# STM32PCB_Sch.net
KiCad netlist of a schematic drawn in Altium Designer
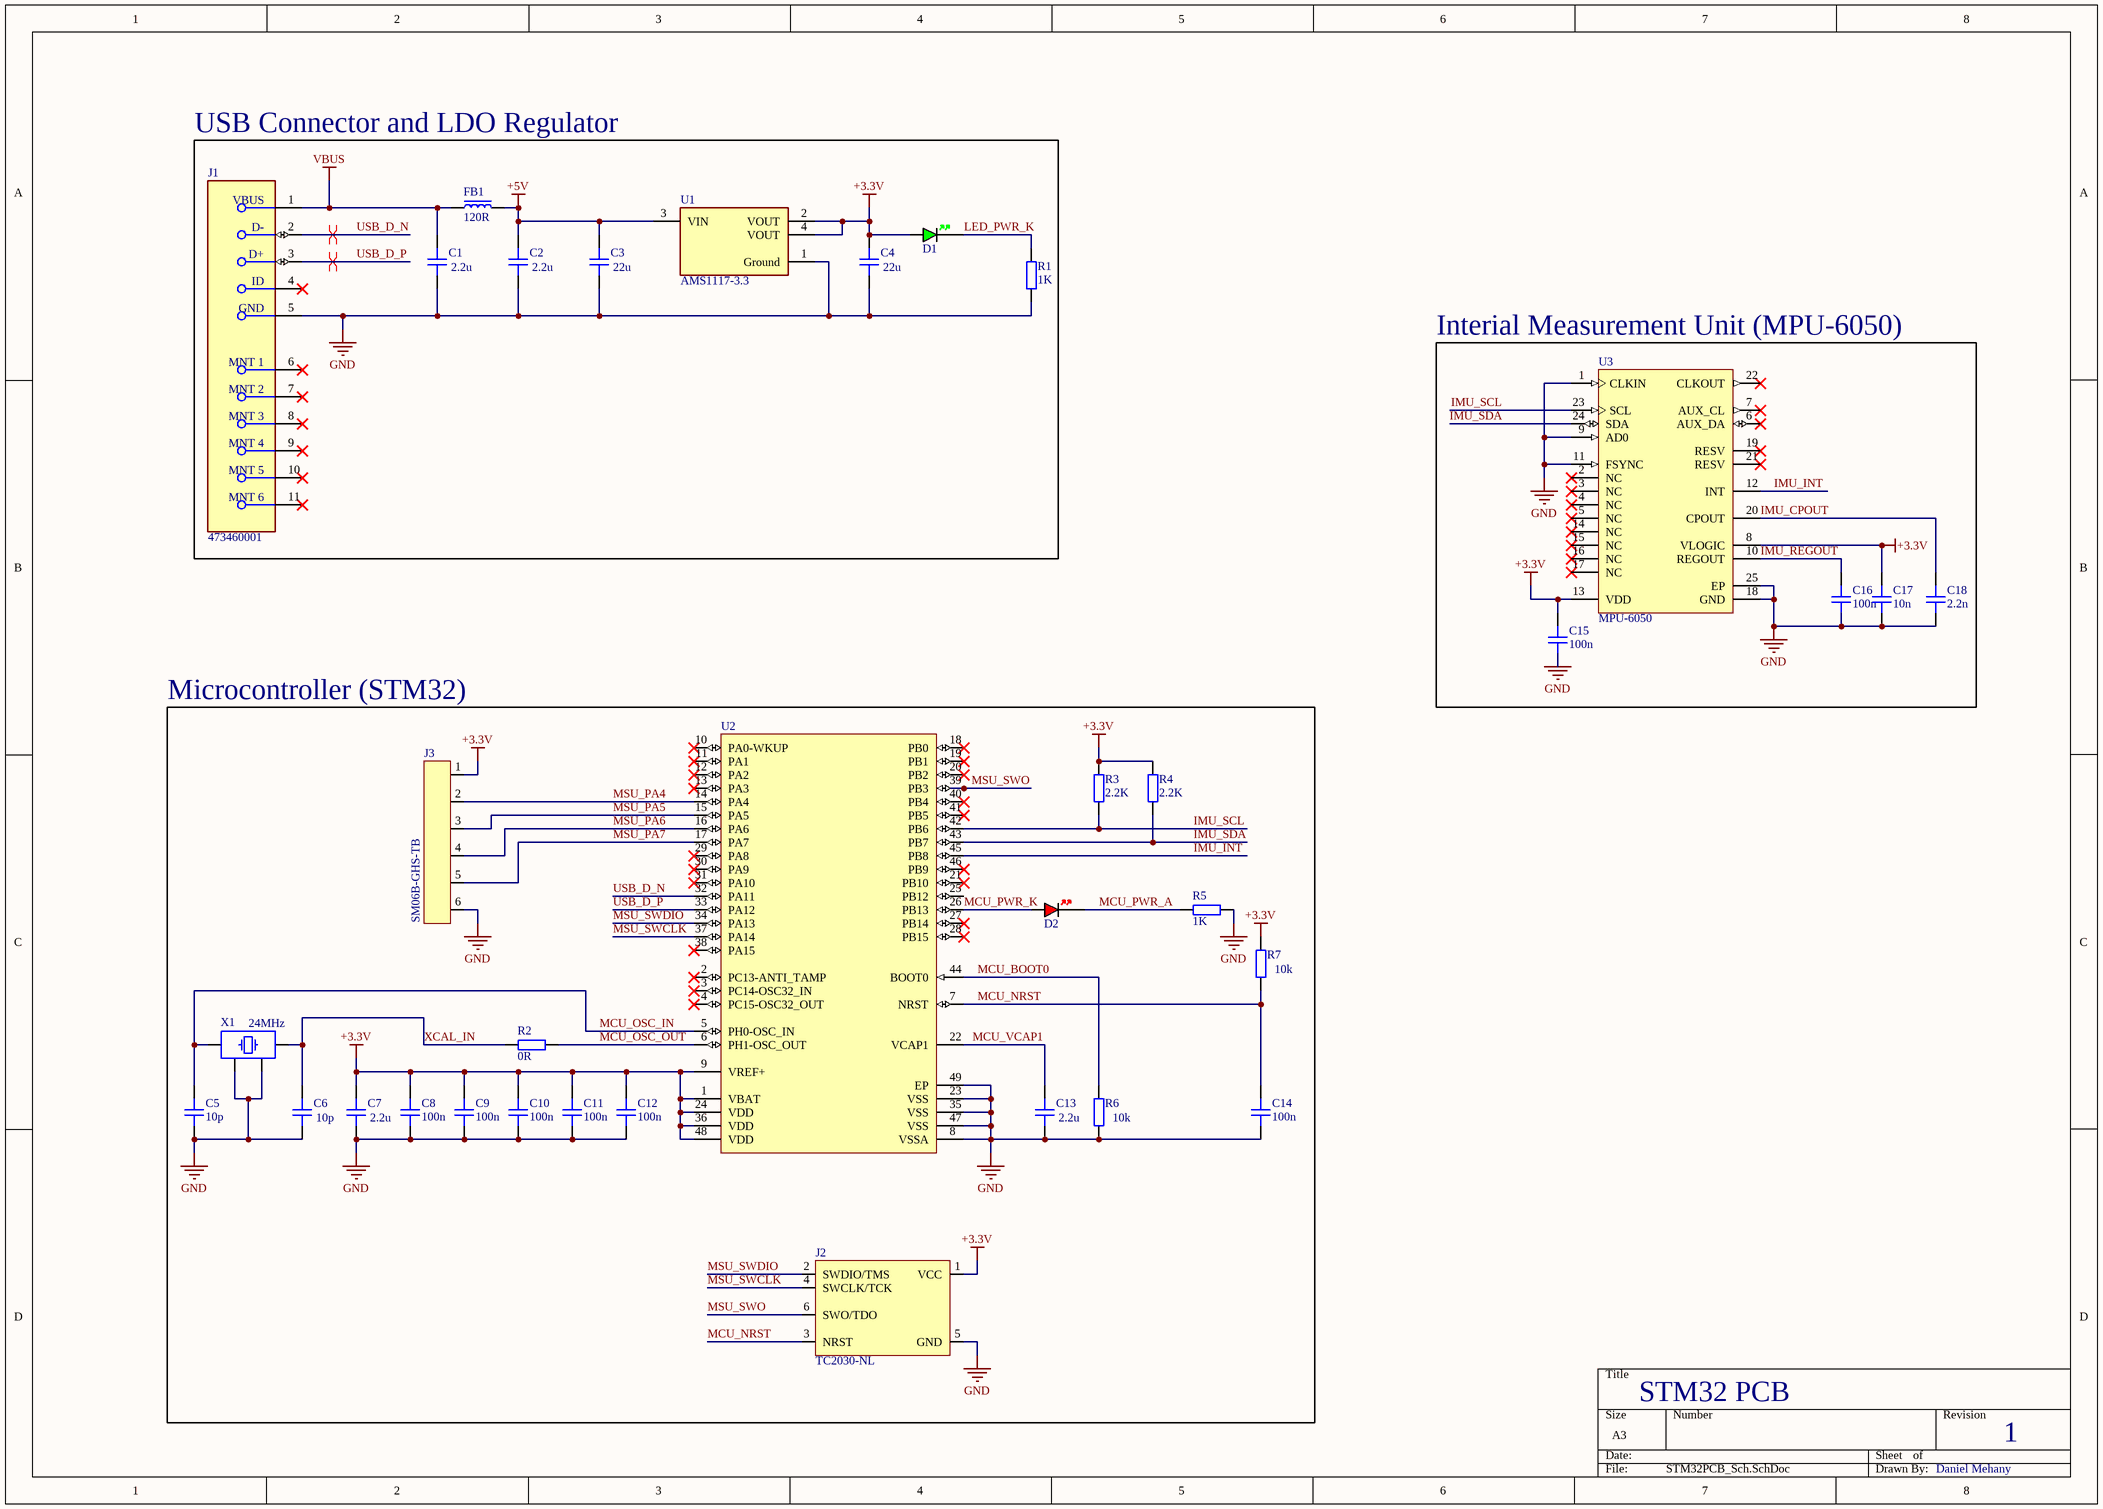
[diagram p0: STM32PCB_Sch.SchDoc]

(export (version "E")
  (design (tool "Eeschema 10.0.6"))
  (components
    (comp (ref "C1")
      (value "2.2u")
      (footprint "CAP_0603")
      (description "Capacitor SMD 0603")
      (libsource (lib "Online_Schematic_Library") (part "CAP_0603"))
    )
    (comp (ref "C2")
      (value "2.2u")
      (footprint "CAP_0603")
      (description "Capacitor SMD 0603")
      (libsource (lib "Online_Schematic_Library") (part "CAP_0603"))
    )
    (comp (ref "C3")
      (value "22u")
      (footprint "CAP_0603")
      (description "Capacitor SMD 0603")
      (libsource (lib "Online_Schematic_Library") (part "CAP_0603"))
    )
    (comp (ref "C4")
      (value "22u")
      (footprint "CAP_0603")
      (description "Capacitor SMD 0603")
      (libsource (lib "Online_Schematic_Library") (part "CAP_0603"))
    )
    (comp (ref "C5")
      (value "10p")
      (footprint "CAP_0402")
      (description "Capacitor SMD 0402")
      (libsource (lib "Online_Schematic_Library") (part "CAP_0402"))
    )
    (comp (ref "C6")
      (value "10p")
      (footprint "CAP_0402")
      (description "Capacitor SMD 0402")
      (libsource (lib "Online_Schematic_Library") (part "CAP_0402"))
    )
    (comp (ref "C7")
      (value "2.2u")
      (footprint "CAP_0603")
      (description "Capacitor SMD 0603")
      (libsource (lib "Online_Schematic_Library") (part "CAP_0603"))
    )
    (comp (ref "C8")
      (value "100n")
      (footprint "CAP_0402")
      (description "Capacitor SMD 0402")
      (fields (field (name "Comment") "C0402_16V"))
      (libsource (lib "Online_Schematic_Library") (part "CAP_0402"))
    )
    (comp (ref "C9")
      (value "100n")
      (footprint "CAP_0402")
      (description "Capacitor SMD 0402")
      (fields (field (name "Comment") "C0402_16V"))
      (libsource (lib "Online_Schematic_Library") (part "CAP_0402"))
    )
    (comp (ref "C10")
      (value "100n")
      (footprint "CAP_0402")
      (description "Capacitor SMD 0402")
      (fields (field (name "Comment") "C0402_16V"))
      (libsource (lib "Online_Schematic_Library") (part "CAP_0402"))
    )
    (comp (ref "C11")
      (value "100n")
      (footprint "CAP_0402")
      (description "Capacitor SMD 0402")
      (fields (field (name "Comment") "C0402_16V"))
      (libsource (lib "Online_Schematic_Library") (part "CAP_0402"))
    )
    (comp (ref "C12")
      (value "100n")
      (footprint "CAP_0402")
      (description "Capacitor SMD 0402")
      (fields (field (name "Comment") "C0402_16V"))
      (libsource (lib "Online_Schematic_Library") (part "CAP_0402"))
    )
    (comp (ref "C13")
      (value "2.2u")
      (footprint "CAP_0603")
      (description "Capacitor SMD 0603")
      (libsource (lib "Online_Schematic_Library") (part "CAP_0603"))
    )
    (comp (ref "C14")
      (value "100n")
      (footprint "CAP_0402")
      (description "Capacitor SMD 0402")
      (fields (field (name "Comment") "C0402_16V"))
      (libsource (lib "Online_Schematic_Library") (part "CAP_0402"))
    )
    (comp (ref "C15")
      (value "100n")
      (footprint "CAP_0402")
      (description "Capacitor SMD 0402")
      (fields (field (name "Comment") "C0402_16V"))
      (libsource (lib "Online_Schematic_Library") (part "CAP_0402"))
    )
    (comp (ref "C16")
      (value "100n")
      (footprint "CAP_0402")
      (description "Capacitor SMD 0402")
      (fields (field (name "Comment") "C0402_16V"))
      (libsource (lib "Online_Schematic_Library") (part "CAP_0402"))
    )
    (comp (ref "C17")
      (value "10n")
      (footprint "CAP_0402")
      (description "Capacitor SMD 0402")
      (fields (field (name "Comment") "C0402_16V"))
      (libsource (lib "Online_Schematic_Library") (part "CAP_0402"))
    )
    (comp (ref "C18")
      (value "2.2n")
      (footprint "CAP_0402")
      (description "Capacitor SMD 0402")
      (fields (field (name "Comment") "C0402_16V"))
      (libsource (lib "Online_Schematic_Library") (part "CAP_0402"))
    )
    (comp (ref "D1")
      (value "GREEN")
      (footprint "LED_0402_GREEN")
      (description "LED 0402 GREEN SMD")
      (libsource (lib "Online_Schematic_Library") (part "LED_0402_GREEN"))
    )
    (comp (ref "D2")
      (value "RED")
      (footprint "LED_0402_RED")
      (description "LED 0402 RED SMD")
      (libsource (lib "Online_Schematic_Library") (part "LED_0402_RED"))
    )
    (comp (ref "FB1")
      (value "120R")
      (footprint "FB_0603")
      (description "Ferrite Bead SMD 0603")
      (libsource (lib "Online_Schematic_Library") (part "FB_0603"))
    )
    (comp (ref "J1")
      (value "473460001")
      (footprint "FP-473460001-MFG")
      (description "CONN RCPT USB2.0 MICRO B SMD R/A")
      (fields
        (field (name "OCTOPART") "https://octopart.com/47346-0001-molex-7164928")
        (field (name "MANUFACTURER") "Molex")
      )
      (libsource (lib "Altium Content Vault") (part "53ae1f1d9b557310b43ca686e5bb76a"))
    )
    (comp (ref "J2")
      (value "TC2030-NL")
      (footprint "TC2030-NL-FP")
      (description "Tag-Connect No-Solder SWD Debug Connector (No Legs) DO NOT PLACE")
      (fields
        (field (name "MANUFACTURER") "Tag-Connect")
        (field (name "MANUFACTURER PART NUMBER") "TC2030-NL-FP")
      )
      (libsource (lib "Online_Schematic_Library") (part "TC2030-NL"))
    )
    (comp (ref "J3")
      (value "SM06B-GHS-TB")
      (footprint "SM06B-GHS-TB")
      (description "Header Connector 6 Position 1.25MM Pitch SMD Horizontal JST GH")
      (fields (field (name "MANUFACTURER") "JST"))
      (libsource (lib "Online_Schematic_Library") (part "SM06B-GHS-TB"))
    )
    (comp (ref "R1")
      (value "1K")
      (footprint "RES_0402")
      (description "Resistor SMD 0402")
      (libsource (lib "Online_Schematic_Library") (part "RES_0402"))
    )
    (comp (ref "R2")
      (value "0R")
      (footprint "RES_0402")
      (description "Resistor SMD 0402")
      (libsource (lib "Online_Schematic_Library") (part "RES_0402"))
    )
    (comp (ref "R3")
      (value "2.2K")
      (footprint "RES_0402")
      (description "Resistor SMD 0402")
      (libsource (lib "Online_Schematic_Library") (part "RES_0402"))
    )
    (comp (ref "R4")
      (value "2.2K")
      (footprint "RES_0402")
      (description "Resistor SMD 0402")
      (libsource (lib "Online_Schematic_Library") (part "RES_0402"))
    )
    (comp (ref "R5")
      (value "1K")
      (footprint "RES_0402")
      (description "Resistor SMD 0402")
      (libsource (lib "Online_Schematic_Library") (part "RES_0402"))
    )
    (comp (ref "R6")
      (value "10k")
      (footprint "RES_0402")
      (description "Resistor SMD 0402")
      (libsource (lib "Online_Schematic_Library") (part "RES_0402"))
    )
    (comp (ref "R7")
      (value "10k")
      (footprint "RES_0402")
      (description "Resistor SMD 0402")
      (libsource (lib "Online_Schematic_Library") (part "RES_0402"))
    )
    (comp (ref "U1")
      (value "AMS1117-3.3")
      (footprint "FP-AMS1117-IPC_C")
      (description "LDO Voltage Regulators 1A, 3.3V")
      (fields
        (field (name "OCTOPART") "https://octopart.com/ams1117-3.3-advanced+monolithic+systems-25899300")
        (field (name "MANUFACTURER") "Advanced Monolithic Systems")
      )
      (libsource (lib "Altium Content Vault") (part "8bdbb5f8e77002000e30dd2845d0354"))
    )
    (comp (ref "U2")
      (value "~")
      (footprint "STM-UFQFPN48_L")
      (libsource (lib "Altium Content Vault") (part "MC-ARM-STM32F411-UFQFPN48"))
    )
    (comp (ref "U3")
      (value "MPU-6050")
      (footprint "IS-QFN-24_V")
      (fields (field (name "MANUFACTURER") "InvenSense"))
      (libsource (lib "Altium Content Vault") (part "IS-MPU-6050-QFN-24"))
    )
    (comp (ref "X1")
      (value "24MHz")
      (footprint "XTAL_3225")
      (description "Crystal SMD 24MHz 10PPM 7pF 3225")
      (fields
        (field (name "MANUFACTURER") "Epson")
        (field (name "MANUFACTURER PART NUMBER") "TSX-3225 24.0000MF15X-AC")
      )
      (libsource (lib "Online_Schematic_Library") (part "TSX-3225_24.0000MF15X-AC"))
    )
  )
  (nets
    (net (code "1") (name "+3.3V") (class "Default")
      (node (ref "C10") (pin "2") (pinfunction "2_2") (pintype "passive"))
      (node (ref "C11") (pin "2") (pinfunction "2_2") (pintype "passive"))
      (node (ref "C12") (pin "2") (pinfunction "2_2") (pintype "passive"))
      (node (ref "C15") (pin "2") (pinfunction "2_2") (pintype "passive"))
      (node (ref "C17") (pin "2") (pinfunction "2_2") (pintype "passive"))
      (node (ref "C4") (pin "2") (pinfunction "2_2") (pintype "passive"))
      (node (ref "C7") (pin "2") (pinfunction "2_2") (pintype "passive"))
      (node (ref "C8") (pin "2") (pinfunction "2_2") (pintype "passive"))
      (node (ref "C9") (pin "2") (pinfunction "2_2") (pintype "passive"))
      (node (ref "D1") (pin "A") (pinfunction "A_A") (pintype "passive"))
      (node (ref "J2") (pin "1") (pinfunction "VCC_1") (pintype "passive"))
      (node (ref "J3") (pin "1") (pinfunction "1_1") (pintype "passive"))
      (node (ref "R3") (pin "2") (pinfunction "2_2") (pintype "passive"))
      (node (ref "R4") (pin "2") (pinfunction "2_2") (pintype "passive"))
      (node (ref "R7") (pin "2") (pinfunction "2_2") (pintype "passive"))
      (node (ref "U1") (pin "2") (pinfunction "VOUT_2") (pintype "passive"))
      (node (ref "U1") (pin "4") (pinfunction "VOUT_4") (pintype "passive"))
      (node (ref "U2") (pin "1") (pinfunction "VBAT_1") (pintype "power_in"))
      (node (ref "U2") (pin "24") (pinfunction "VDD_24") (pintype "power_in"))
      (node (ref "U2") (pin "36") (pinfunction "VDD_36") (pintype "power_in"))
      (node (ref "U2") (pin "48") (pinfunction "VDD_48") (pintype "power_in"))
      (node (ref "U2") (pin "9") (pinfunction "VREF+_9") (pintype "power_in"))
      (node (ref "U3") (pin "13") (pinfunction "VDD_13") (pintype "power_in"))
      (node (ref "U3") (pin "8") (pinfunction "VLOGIC_8") (pintype "power_in"))
    )
    (net (code "2") (name "+5V") (class "Default")
      (node (ref "C2") (pin "2") (pinfunction "2_2") (pintype "passive"))
      (node (ref "C3") (pin "2") (pinfunction "2_2") (pintype "passive"))
      (node (ref "FB1") (pin "2") (pinfunction "2_2") (pintype "passive"))
      (node (ref "U1") (pin "3") (pinfunction "VIN_3") (pintype "power_in"))
    )
    (net (code "3") (name "/IMU_CPOUT") (class "Default")
      (node (ref "C18") (pin "2") (pinfunction "2_2") (pintype "passive"))
      (node (ref "U3") (pin "20") (pinfunction "CPOUT_20") (pintype "passive"))
    )
    (net (code "4") (name "/IMU_INT") (class "Default")
      (node (ref "U2") (pin "45") (pinfunction "PB8_45") (pintype "bidirectional"))
      (node (ref "U3") (pin "12") (pinfunction "INT_12") (pintype "open_collector"))
    )
    (net (code "5") (name "/IMU_REGOUT") (class "Default")
      (node (ref "C16") (pin "2") (pinfunction "2_2") (pintype "passive"))
      (node (ref "U3") (pin "10") (pinfunction "REGOUT_10") (pintype "passive"))
    )
    (net (code "6") (name "/IMU_SCL") (class "Default")
      (node (ref "R3") (pin "1") (pinfunction "1_1") (pintype "passive"))
      (node (ref "U2") (pin "42") (pinfunction "PB6_42") (pintype "bidirectional"))
      (node (ref "U3") (pin "23") (pinfunction "SCL_23") (pintype "input"))
    )
    (net (code "7") (name "/IMU_SDA") (class "Default")
      (node (ref "R4") (pin "1") (pinfunction "1_1") (pintype "passive"))
      (node (ref "U2") (pin "43") (pinfunction "PB7_43") (pintype "bidirectional"))
      (node (ref "U3") (pin "24") (pinfunction "SDA_24") (pintype "bidirectional"))
    )
    (net (code "8") (name "/LED_PWR_K") (class "Default")
      (node (ref "D1") (pin "K") (pinfunction "K_K") (pintype "passive"))
      (node (ref "R1") (pin "2") (pinfunction "2_2") (pintype "passive"))
    )
    (net (code "9") (name "/MCU_BOOT0") (class "Default")
      (node (ref "R6") (pin "2") (pinfunction "2_2") (pintype "passive"))
      (node (ref "U2") (pin "44") (pinfunction "BOOT0_44") (pintype "input"))
    )
    (net (code "10") (name "/MCU_NRST") (class "Default")
      (node (ref "C14") (pin "2") (pinfunction "2_2") (pintype "passive"))
      (node (ref "J2") (pin "3") (pinfunction "NRST_3") (pintype "passive"))
      (node (ref "R7") (pin "1") (pinfunction "1_1") (pintype "passive"))
      (node (ref "U2") (pin "7") (pinfunction "NRST_7") (pintype "bidirectional"))
    )
    (net (code "11") (name "/MCU_OSC_IN") (class "Default")
      (node (ref "C5") (pin "2") (pinfunction "2_2") (pintype "passive"))
      (node (ref "U2") (pin "5") (pinfunction "PH0-OSC_IN_5") (pintype "bidirectional"))
      (node (ref "X1") (pin "1") (pinfunction "1_1") (pintype "passive"))
    )
    (net (code "12") (name "/MCU_OSC_OUT") (class "Default")
      (node (ref "R2") (pin "2") (pinfunction "2_2") (pintype "passive"))
      (node (ref "U2") (pin "6") (pinfunction "PH1-OSC_OUT_6") (pintype "bidirectional"))
    )
    (net (code "13") (name "/MCU_PWR_A") (class "Default")
      (node (ref "D2") (pin "K") (pinfunction "K_K") (pintype "passive"))
      (node (ref "R5") (pin "2") (pinfunction "2_2") (pintype "passive"))
    )
    (net (code "14") (name "/MCU_PWR_K") (class "Default")
      (node (ref "D2") (pin "A") (pinfunction "A_A") (pintype "passive"))
      (node (ref "U2") (pin "26") (pinfunction "PB13_26") (pintype "bidirectional"))
    )
    (net (code "15") (name "/MCU_VCAP1") (class "Default")
      (node (ref "C13") (pin "2") (pinfunction "2_2") (pintype "passive"))
      (node (ref "U2") (pin "22") (pinfunction "VCAP1_22") (pintype "passive"))
    )
    (net (code "16") (name "/MSU_PA4") (class "Default")
      (node (ref "J3") (pin "2") (pinfunction "2_2") (pintype "passive"))
      (node (ref "U2") (pin "14") (pinfunction "PA4_14") (pintype "bidirectional"))
    )
    (net (code "17") (name "/MSU_PA5") (class "Default")
      (node (ref "J3") (pin "3") (pinfunction "3_3") (pintype "passive"))
      (node (ref "U2") (pin "15") (pinfunction "PA5_15") (pintype "bidirectional"))
    )
    (net (code "18") (name "/MSU_PA6") (class "Default")
      (node (ref "J3") (pin "4") (pinfunction "4_4") (pintype "passive"))
      (node (ref "U2") (pin "16") (pinfunction "PA6_16") (pintype "bidirectional"))
    )
    (net (code "19") (name "/MSU_PA7") (class "Default")
      (node (ref "J3") (pin "5") (pinfunction "5_5") (pintype "passive"))
      (node (ref "U2") (pin "17") (pinfunction "PA7_17") (pintype "bidirectional"))
    )
    (net (code "20") (name "/MSU_SWCLK") (class "Default")
      (node (ref "J2") (pin "4") (pinfunction "SWCLK/TCK_4") (pintype "passive"))
      (node (ref "U2") (pin "37") (pinfunction "PA14_37") (pintype "bidirectional"))
    )
    (net (code "21") (name "/MSU_SWDIO") (class "Default")
      (node (ref "J2") (pin "2") (pinfunction "SWDIO/TMS_2") (pintype "passive"))
      (node (ref "U2") (pin "34") (pinfunction "PA13_34") (pintype "bidirectional"))
    )
    (net (code "22") (name "/MSU_SWO") (class "Default")
      (node (ref "J2") (pin "6") (pinfunction "SWO/TDO_6") (pintype "passive"))
      (node (ref "U2") (pin "39") (pinfunction "PB3_39") (pintype "bidirectional"))
    )
    (net (code "23") (name "/USB_D_N") (class "Default")
      (node (ref "J1") (pin "2") (pinfunction "D-_2") (pintype "bidirectional"))
      (node (ref "U2") (pin "32") (pinfunction "PA11_32") (pintype "bidirectional"))
    )
    (net (code "24") (name "/USB_D_P") (class "Default")
      (node (ref "J1") (pin "3") (pinfunction "D+_3") (pintype "bidirectional"))
      (node (ref "U2") (pin "33") (pinfunction "PA12_33") (pintype "bidirectional"))
    )
    (net (code "25") (name "/XCAL_IN") (class "Default")
      (node (ref "C6") (pin "2") (pinfunction "2_2") (pintype "passive"))
      (node (ref "R2") (pin "1") (pinfunction "1_1") (pintype "passive"))
      (node (ref "X1") (pin "3") (pinfunction "3_3") (pintype "passive"))
    )
    (net (code "26") (name "GND") (class "Default")
      (node (ref "C1") (pin "1") (pinfunction "1_1") (pintype "passive"))
      (node (ref "C10") (pin "1") (pinfunction "1_1") (pintype "passive"))
      (node (ref "C11") (pin "1") (pinfunction "1_1") (pintype "passive"))
      (node (ref "C12") (pin "1") (pinfunction "1_1") (pintype "passive"))
      (node (ref "C13") (pin "1") (pinfunction "1_1") (pintype "passive"))
      (node (ref "C14") (pin "1") (pinfunction "1_1") (pintype "passive"))
      (node (ref "C15") (pin "1") (pinfunction "1_1") (pintype "passive"))
      (node (ref "C16") (pin "1") (pinfunction "1_1") (pintype "passive"))
      (node (ref "C17") (pin "1") (pinfunction "1_1") (pintype "passive"))
      (node (ref "C18") (pin "1") (pinfunction "1_1") (pintype "passive"))
      (node (ref "C2") (pin "1") (pinfunction "1_1") (pintype "passive"))
      (node (ref "C3") (pin "1") (pinfunction "1_1") (pintype "passive"))
      (node (ref "C4") (pin "1") (pinfunction "1_1") (pintype "passive"))
      (node (ref "C5") (pin "1") (pinfunction "1_1") (pintype "passive"))
      (node (ref "C6") (pin "1") (pinfunction "1_1") (pintype "passive"))
      (node (ref "C7") (pin "1") (pinfunction "1_1") (pintype "passive"))
      (node (ref "C8") (pin "1") (pinfunction "1_1") (pintype "passive"))
      (node (ref "C9") (pin "1") (pinfunction "1_1") (pintype "passive"))
      (node (ref "J1") (pin "5") (pinfunction "GND_5") (pintype "power_in"))
      (node (ref "J2") (pin "5") (pinfunction "GND_5") (pintype "passive"))
      (node (ref "J3") (pin "6") (pinfunction "6_6") (pintype "passive"))
      (node (ref "R1") (pin "1") (pinfunction "1_1") (pintype "passive"))
      (node (ref "R5") (pin "1") (pinfunction "1_1") (pintype "passive"))
      (node (ref "R6") (pin "1") (pinfunction "1_1") (pintype "passive"))
      (node (ref "U1") (pin "1") (pinfunction "Ground_1") (pintype "power_in"))
      (node (ref "U2") (pin "23") (pinfunction "VSS_23") (pintype "power_in"))
      (node (ref "U2") (pin "35") (pinfunction "VSS_35") (pintype "power_in"))
      (node (ref "U2") (pin "47") (pinfunction "VSS_47") (pintype "power_in"))
      (node (ref "U2") (pin "49") (pinfunction "EP_49") (pintype "power_in"))
      (node (ref "U2") (pin "8") (pinfunction "VSSA_8") (pintype "power_in"))
      (node (ref "U3") (pin "1") (pinfunction "CLKIN_1") (pintype "input"))
      (node (ref "U3") (pin "11") (pinfunction "FSYNC_11") (pintype "input"))
      (node (ref "U3") (pin "18") (pinfunction "GND_18") (pintype "power_in"))
      (node (ref "U3") (pin "25") (pinfunction "EP_25") (pintype "power_in"))
      (node (ref "U3") (pin "9") (pinfunction "AD0_9") (pintype "input"))
      (node (ref "X1") (pin "2") (pinfunction "2_2") (pintype "passive"))
      (node (ref "X1") (pin "4") (pinfunction "4_4") (pintype "passive"))
    )
    (net (code "27") (name "VBUS") (class "Default")
      (node (ref "C1") (pin "2") (pinfunction "2_2") (pintype "passive"))
      (node (ref "FB1") (pin "1") (pinfunction "1_1") (pintype "passive"))
      (node (ref "J1") (pin "1") (pinfunction "VBUS_1") (pintype "power_in"))
    )
    (net (code "28") (name "unconnected-(J1-ID-Pad4)") (class "Default")
      (node (ref "J1") (pin "4") (pinfunction "ID_4") (pintype "passive+no_connect"))
    )
    (net (code "29") (name "unconnected-(J1-MNT_1-Pad6)") (class "Default")
      (node (ref "J1") (pin "6") (pinfunction "MNT_1_6") (pintype "passive+no_connect"))
    )
    (net (code "30") (name "unconnected-(J1-MNT_2-Pad7)") (class "Default")
      (node (ref "J1") (pin "7") (pinfunction "MNT_2_7") (pintype "passive+no_connect"))
    )
    (net (code "31") (name "unconnected-(J1-MNT_3-Pad8)") (class "Default")
      (node (ref "J1") (pin "8") (pinfunction "MNT_3_8") (pintype "passive+no_connect"))
    )
    (net (code "32") (name "unconnected-(J1-MNT_4-Pad9)") (class "Default")
      (node (ref "J1") (pin "9") (pinfunction "MNT_4_9") (pintype "passive+no_connect"))
    )
    (net (code "33") (name "unconnected-(J1-MNT_5-Pad10)") (class "Default")
      (node (ref "J1") (pin "10") (pinfunction "MNT_5_10") (pintype "passive+no_connect"))
    )
    (net (code "34") (name "unconnected-(J1-MNT_6-Pad11)") (class "Default")
      (node (ref "J1") (pin "11") (pinfunction "MNT_6_11") (pintype "passive+no_connect"))
    )
    (net (code "35") (name "unconnected-(U2-PA0-WKUP-Pad10)") (class "Default")
      (node (ref "U2") (pin "10") (pinfunction "PA0-WKUP_10") (pintype "bidirectional+no_connect"))
    )
    (net (code "36") (name "unconnected-(U2-PA1-Pad11)") (class "Default")
      (node (ref "U2") (pin "11") (pinfunction "PA1_11") (pintype "bidirectional+no_connect"))
    )
    (net (code "37") (name "unconnected-(U2-PA2-Pad12)") (class "Default")
      (node (ref "U2") (pin "12") (pinfunction "PA2_12") (pintype "bidirectional+no_connect"))
    )
    (net (code "38") (name "unconnected-(U2-PA3-Pad13)") (class "Default")
      (node (ref "U2") (pin "13") (pinfunction "PA3_13") (pintype "bidirectional+no_connect"))
    )
    (net (code "39") (name "unconnected-(U2-PA8-Pad29)") (class "Default")
      (node (ref "U2") (pin "29") (pinfunction "PA8_29") (pintype "bidirectional+no_connect"))
    )
    (net (code "40") (name "unconnected-(U2-PA9-Pad30)") (class "Default")
      (node (ref "U2") (pin "30") (pinfunction "PA9_30") (pintype "bidirectional+no_connect"))
    )
    (net (code "41") (name "unconnected-(U2-PA10-Pad31)") (class "Default")
      (node (ref "U2") (pin "31") (pinfunction "PA10_31") (pintype "bidirectional+no_connect"))
    )
    (net (code "42") (name "unconnected-(U2-PA15-Pad38)") (class "Default")
      (node (ref "U2") (pin "38") (pinfunction "PA15_38") (pintype "bidirectional+no_connect"))
    )
    (net (code "43") (name "unconnected-(U2-PB0-Pad18)") (class "Default")
      (node (ref "U2") (pin "18") (pinfunction "PB0_18") (pintype "bidirectional+no_connect"))
    )
    (net (code "44") (name "unconnected-(U2-PB1-Pad19)") (class "Default")
      (node (ref "U2") (pin "19") (pinfunction "PB1_19") (pintype "bidirectional+no_connect"))
    )
    (net (code "45") (name "unconnected-(U2-PB2-Pad20)") (class "Default")
      (node (ref "U2") (pin "20") (pinfunction "PB2_20") (pintype "bidirectional+no_connect"))
    )
    (net (code "46") (name "unconnected-(U2-PB4-Pad40)") (class "Default")
      (node (ref "U2") (pin "40") (pinfunction "PB4_40") (pintype "bidirectional+no_connect"))
    )
    (net (code "47") (name "unconnected-(U2-PB5-Pad41)") (class "Default")
      (node (ref "U2") (pin "41") (pinfunction "PB5_41") (pintype "bidirectional+no_connect"))
    )
    (net (code "48") (name "unconnected-(U2-PB9-Pad46)") (class "Default")
      (node (ref "U2") (pin "46") (pinfunction "PB9_46") (pintype "bidirectional+no_connect"))
    )
    (net (code "49") (name "unconnected-(U2-PB10-Pad21)") (class "Default")
      (node (ref "U2") (pin "21") (pinfunction "PB10_21") (pintype "bidirectional+no_connect"))
    )
    (net (code "50") (name "unconnected-(U2-PB12-Pad25)") (class "Default")
      (node (ref "U2") (pin "25") (pinfunction "PB12_25") (pintype "bidirectional"))
    )
    (net (code "51") (name "unconnected-(U2-PB14-Pad27)") (class "Default")
      (node (ref "U2") (pin "27") (pinfunction "PB14_27") (pintype "bidirectional+no_connect"))
    )
    (net (code "52") (name "unconnected-(U2-PB15-Pad28)") (class "Default")
      (node (ref "U2") (pin "28") (pinfunction "PB15_28") (pintype "bidirectional+no_connect"))
    )
    (net (code "53") (name "unconnected-(U2-PC13-ANTI_TAMP-Pad2)") (class "Default")
      (node (ref "U2") (pin "2") (pinfunction "PC13-ANTI_TAMP_2") (pintype "bidirectional+no_connect"))
    )
    (net (code "54") (name "unconnected-(U2-PC14-OSC32_IN-Pad3)") (class "Default")
      (node (ref "U2") (pin "3") (pinfunction "PC14-OSC32_IN_3") (pintype "bidirectional+no_connect"))
    )
    (net (code "55") (name "unconnected-(U2-PC15-OSC32_OUT-Pad4)") (class "Default")
      (node (ref "U2") (pin "4") (pinfunction "PC15-OSC32_OUT_4") (pintype "bidirectional+no_connect"))
    )
    (net (code "56") (name "unconnected-(U3-AUX_CL-Pad7)") (class "Default")
      (node (ref "U3") (pin "7") (pinfunction "AUX_CL_7") (pintype "output+no_connect"))
    )
    (net (code "57") (name "unconnected-(U3-AUX_DA-Pad6)") (class "Default")
      (node (ref "U3") (pin "6") (pinfunction "AUX_DA_6") (pintype "bidirectional+no_connect"))
    )
    (net (code "58") (name "unconnected-(U3-CLKOUT-Pad22)") (class "Default")
      (node (ref "U3") (pin "22") (pinfunction "CLKOUT_22") (pintype "output+no_connect"))
    )
    (net (code "59") (name "unconnected-(U3-NC-Pad2)") (class "Default")
      (node (ref "U3") (pin "2") (pinfunction "NC_2") (pintype "passive+no_connect"))
    )
    (net (code "60") (name "unconnected-(U3-NC-Pad3)") (class "Default")
      (node (ref "U3") (pin "3") (pinfunction "NC_3") (pintype "passive+no_connect"))
    )
    (net (code "61") (name "unconnected-(U3-NC-Pad4)") (class "Default")
      (node (ref "U3") (pin "4") (pinfunction "NC_4") (pintype "passive+no_connect"))
    )
    (net (code "62") (name "unconnected-(U3-NC-Pad5)") (class "Default")
      (node (ref "U3") (pin "5") (pinfunction "NC_5") (pintype "passive+no_connect"))
    )
    (net (code "63") (name "unconnected-(U3-NC-Pad14)") (class "Default")
      (node (ref "U3") (pin "14") (pinfunction "NC_14") (pintype "passive+no_connect"))
    )
    (net (code "64") (name "unconnected-(U3-NC-Pad15)") (class "Default")
      (node (ref "U3") (pin "15") (pinfunction "NC_15") (pintype "passive+no_connect"))
    )
    (net (code "65") (name "unconnected-(U3-NC-Pad16)") (class "Default")
      (node (ref "U3") (pin "16") (pinfunction "NC_16") (pintype "passive+no_connect"))
    )
    (net (code "66") (name "unconnected-(U3-NC-Pad17)") (class "Default")
      (node (ref "U3") (pin "17") (pinfunction "NC_17") (pintype "passive+no_connect"))
    )
    (net (code "67") (name "unconnected-(U3-RESV-Pad19)") (class "Default")
      (node (ref "U3") (pin "19") (pinfunction "RESV_19") (pintype "passive+no_connect"))
    )
    (net (code "68") (name "unconnected-(U3-RESV-Pad21)") (class "Default")
      (node (ref "U3") (pin "21") (pinfunction "RESV_21") (pintype "passive+no_connect"))
    )
  )
)
